# RF_T-Line.net
KiCad netlist of a schematic drawn in Altium Designer
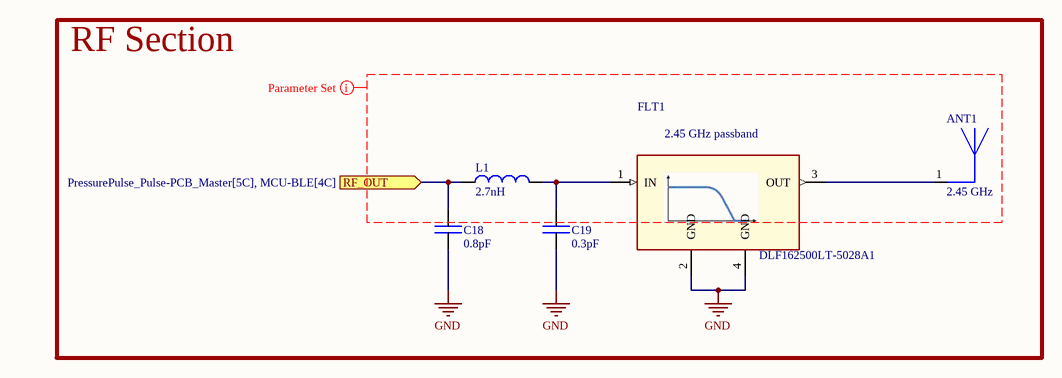
[diagram p0: RF_T-Line.SchDoc]

(export (version "E")
  (design (tool "Eeschema 10.0.6"))
  (components
    (comp (ref "ANT1")
      (value "CHIP ANTENNA")
      (footprint "PressurePulse:ANTC5220X130N")
      (fields (field (name "MFR") "Pulse Electronics") (field (name "CENTER FREQUENCY") "2.45 GHz"))
      (libsource (lib "PressurePulse") (part "CHIP ANTENNA"))
    )
    (comp (ref "C18")
      (value "0.8pF")
      (footprint "PressurePulse:0603C")
      (description "Capacitor")
      (fields (field (name "Comment") "CAP"))
      (libsource (lib "PressurePulse") (part "CAP"))
    )
    (comp (ref "C19")
      (value "0.3pF")
      (footprint "PressurePulse:0402C")
      (description "Capacitor")
      (fields (field (name "Comment") "CAP"))
      (libsource (lib "PressurePulse") (part "CAP"))
    )
    (comp (ref "FLT1")
      (value "DLF162500LT-5028A1")
      (footprint "PressurePulse:DLF-4_1P6X0P8")
      (description "RF FILTER LOW PASS 2.45GHZ 0603")
      (fields (field (name "MFR") "TDK"))
      (libsource (lib "PressurePulse") (part "2.45GHz LPF"))
    )
    (comp (ref "L1")
      (value "2.7nH")
      (footprint "PressurePulse:0402L")
      (description "INDUCTOR")
      (fields (field (name "Comment") "IND"))
      (libsource (lib "PressurePulse") (part "IND"))
    )
  )
  (nets
    (net (code "1") (name "/RF_OUT") (class "Default")
      (node (ref "C18") (pin "2") (pinfunction "2_2") (pintype "passive"))
      (node (ref "L1") (pin "1") (pinfunction "1_1") (pintype "passive"))
    )
    (net (code "2") (name "GND") (class "Default")
      (node (ref "C18") (pin "1") (pinfunction "1_1") (pintype "passive"))
      (node (ref "C19") (pin "1") (pinfunction "1_1") (pintype "passive"))
      (node (ref "FLT1") (pin "2") (pinfunction "GND_2") (pintype "power_in"))
      (node (ref "FLT1") (pin "4") (pinfunction "GND_4") (pintype "power_in"))
    )
    (net (code "3") (name "Net-(FLT1-IN)") (class "Default")
      (node (ref "C19") (pin "2") (pinfunction "2_2") (pintype "passive"))
      (node (ref "FLT1") (pin "1") (pinfunction "IN_1") (pintype "input"))
      (node (ref "L1") (pin "2") (pinfunction "2_2") (pintype "passive"))
    )
    (net (code "4") (name "Net-(FLT1-OUT)") (class "Default")
      (node (ref "ANT1") (pin "1") (pinfunction "1_1") (pintype "passive"))
      (node (ref "FLT1") (pin "3") (pinfunction "OUT_3") (pintype "output"))
    )
  )
)
